# UniAdapter.net
KiCad netlist of a schematic drawn in EAGLE
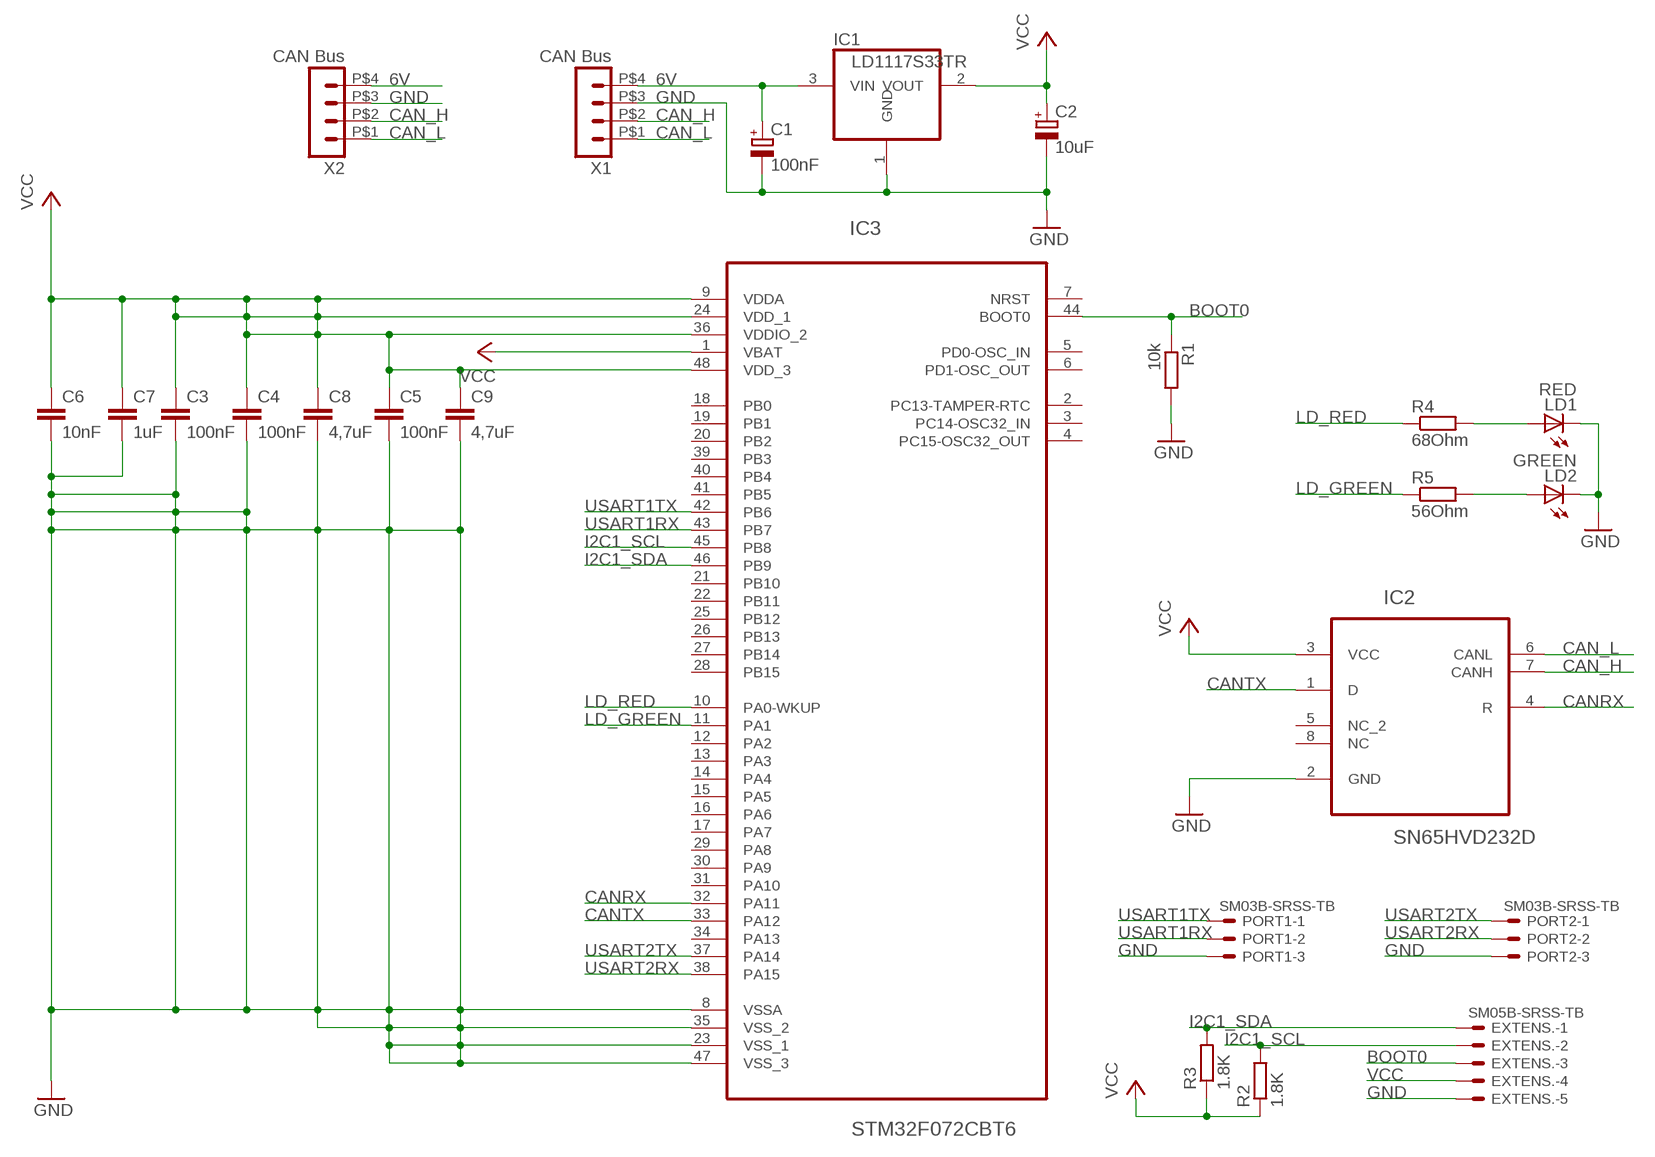
[diagram p0: schematic, sheet 1]

(export (version "E")
  (design (tool "Eeschema 10.0.6"))
  (components
    (comp (ref "C1")
      (value "100nF")
      (footprint "eagle-import:CT3216")
      (libsource (lib "eagle-import") (part "CPOL-EUCT3216"))
    )
    (comp (ref "C2")
      (value "10uF")
      (footprint "eagle-import:CT3216")
      (libsource (lib "eagle-import") (part "CPOL-EUCT3216"))
    )
    (comp (ref "C3")
      (value "100nF")
      (footprint "eagle-import:C0603")
      (libsource (lib "eagle-import") (part "C-EUC0603"))
    )
    (comp (ref "C4")
      (value "100nF")
      (footprint "eagle-import:C0603")
      (libsource (lib "eagle-import") (part "C-EUC0603"))
    )
    (comp (ref "C5")
      (value "100nF")
      (footprint "eagle-import:C0603")
      (libsource (lib "eagle-import") (part "C-EUC0603"))
    )
    (comp (ref "C6")
      (value "10nF")
      (footprint "eagle-import:C0603")
      (libsource (lib "eagle-import") (part "C-EUC0603"))
    )
    (comp (ref "C7")
      (value "1uF")
      (footprint "eagle-import:C0603")
      (libsource (lib "eagle-import") (part "C-EUC0603"))
    )
    (comp (ref "C8")
      (value "4,7uF")
      (footprint "eagle-import:C0603")
      (libsource (lib "eagle-import") (part "C-EUC0603"))
    )
    (comp (ref "C9")
      (value "4,7uF")
      (footprint "eagle-import:C0603")
      (libsource (lib "eagle-import") (part "C-EUC0603"))
    )
    (comp (ref "EXTENS.")
      (value "SM05B-SRSS-TB")
      (footprint "eagle-import:SM05B-SRSS-TB")
      (libsource (lib "eagle-import") (part "?M05B-SRSS-TBS"))
    )
    (comp (ref "IC1")
      (value "LD1117S33TR")
      (footprint "eagle-import:SOT223")
      (fields (field (name "MF") "STMICROELECTRONICS") (field (name "MPN") "REG1117"))
      (libsource (lib "eagle-import") (part "LD1117S33TR"))
    )
    (comp (ref "IC2")
      (value "SN65HVD232D")
      (footprint "eagle-import:SOIC127P600X175-8N")
      (libsource (lib "eagle-import") (part "SN65HVD232D"))
    )
    (comp (ref "IC3")
      (value "STM32F072CBT6")
      (footprint "eagle-import:LQFP48")
      (libsource (lib "eagle-import") (part "STM32F072CBT6"))
    )
    (comp (ref "LD1")
      (value "RED")
      (footprint "eagle-import:CHIPLED_0603")
      (libsource (lib "eagle-import") (part "LEDCHIPLED_0603"))
    )
    (comp (ref "LD2")
      (value "GREEN")
      (footprint "eagle-import:CHIPLED_0603")
      (libsource (lib "eagle-import") (part "LEDCHIPLED_0603"))
    )
    (comp (ref "PORT1")
      (value "SM03B-SRSS-TB")
      (footprint "eagle-import:SM03B-SRSS-TB")
      (libsource (lib "eagle-import") (part "?M03B-SRSS-TBS"))
    )
    (comp (ref "PORT2")
      (value "SM03B-SRSS-TB")
      (footprint "eagle-import:SM03B-SRSS-TB")
      (libsource (lib "eagle-import") (part "?M03B-SRSS-TBS"))
    )
    (comp (ref "R1")
      (value "10k")
      (footprint "eagle-import:R0603")
      (libsource (lib "eagle-import") (part "R-EU_R0603"))
    )
    (comp (ref "R2")
      (value "1.8K")
      (footprint "eagle-import:R0603")
      (libsource (lib "eagle-import") (part "R-EU_R0603"))
    )
    (comp (ref "R3")
      (value "1.8K")
      (footprint "eagle-import:R0603")
      (libsource (lib "eagle-import") (part "R-EU_R0603"))
    )
    (comp (ref "R4")
      (value "68Ohm")
      (footprint "eagle-import:R0603")
      (libsource (lib "eagle-import") (part "R-EU_R0603"))
    )
    (comp (ref "R5")
      (value "56Ohm")
      (footprint "eagle-import:R0603")
      (libsource (lib "eagle-import") (part "R-EU_R0603"))
    )
    (comp (ref "X1")
      (value "CAN Bus")
      (footprint "eagle-import:43650-0412")
      (libsource (lib "eagle-import") (part "HEADER_POS4_?43650-0412"))
    )
    (comp (ref "X2")
      (value "CAN Bus")
      (footprint "eagle-import:43650-0412")
      (libsource (lib "eagle-import") (part "HEADER_POS4_?43650-0412"))
    )
  )
  (nets
    (net (code "1") (name "/6V") (class "Default")
      (node (ref "C1") (pin "+") (pinfunction "+_+") (pintype "passive"))
      (node (ref "IC1") (pin "3") (pinfunction "VIN_3") (pintype "input"))
      (node (ref "X1") (pin "P$4") (pinfunction "4_P$4") (pintype "passive"))
      (node (ref "X2") (pin "P$4") (pinfunction "4_P$4") (pintype "passive"))
    )
    (net (code "2") (name "/BOOT0") (class "Default")
      (node (ref "EXTENS.") (pin "3") (pinfunction "S_3") (pintype "passive"))
      (node (ref "IC3") (pin "44") (pinfunction "BOOT0_44") (pintype "bidirectional"))
      (node (ref "R1") (pin "1") (pinfunction "1_1") (pintype "passive"))
    )
    (net (code "3") (name "/CANRX") (class "Default")
      (node (ref "IC2") (pin "4") (pinfunction "R_4") (pintype "output"))
      (node (ref "IC3") (pin "32") (pinfunction "PA11_32") (pintype "power_in"))
    )
    (net (code "4") (name "/CANTX") (class "Default")
      (node (ref "IC2") (pin "1") (pinfunction "D_1") (pintype "input"))
      (node (ref "IC3") (pin "33") (pinfunction "PA12_33") (pintype "bidirectional"))
    )
    (net (code "5") (name "/CAN_H") (class "Default")
      (node (ref "IC2") (pin "7") (pinfunction "CANH_7") (pintype "output"))
      (node (ref "X1") (pin "P$2") (pinfunction "2_P$2") (pintype "passive"))
      (node (ref "X2") (pin "P$2") (pinfunction "2_P$2") (pintype "passive"))
    )
    (net (code "6") (name "/CAN_L") (class "Default")
      (node (ref "IC2") (pin "6") (pinfunction "CANL_6") (pintype "output"))
      (node (ref "X1") (pin "P$1") (pinfunction "1_P$1") (pintype "passive"))
      (node (ref "X2") (pin "P$1") (pinfunction "1_P$1") (pintype "passive"))
    )
    (net (code "7") (name "/I2C1_SCL") (class "Default")
      (node (ref "EXTENS.") (pin "2") (pinfunction "S_2") (pintype "passive"))
      (node (ref "IC3") (pin "45") (pinfunction "PB8_45") (pintype "bidirectional"))
      (node (ref "R2") (pin "2") (pinfunction "2_2") (pintype "passive"))
    )
    (net (code "8") (name "/I2C1_SDA") (class "Default")
      (node (ref "EXTENS.") (pin "1") (pinfunction "S_1") (pintype "passive"))
      (node (ref "IC3") (pin "46") (pinfunction "PB9_46") (pintype "bidirectional"))
      (node (ref "R3") (pin "2") (pinfunction "2_2") (pintype "passive"))
    )
    (net (code "9") (name "/LD_GREEN") (class "Default")
      (node (ref "IC3") (pin "11") (pinfunction "PA1_11") (pintype "bidirectional"))
      (node (ref "R5") (pin "1") (pinfunction "1_1") (pintype "passive"))
    )
    (net (code "10") (name "/LD_RED") (class "Default")
      (node (ref "IC3") (pin "10") (pinfunction "PA0-WKUP_10") (pintype "bidirectional"))
      (node (ref "R4") (pin "1") (pinfunction "1_1") (pintype "passive"))
    )
    (net (code "11") (name "/USART1RX") (class "Default")
      (node (ref "IC3") (pin "43") (pinfunction "PB7_43") (pintype "bidirectional"))
      (node (ref "PORT1") (pin "2") (pinfunction "S_2") (pintype "passive"))
    )
    (net (code "12") (name "/USART1TX") (class "Default")
      (node (ref "IC3") (pin "42") (pinfunction "PB6_42") (pintype "bidirectional"))
      (node (ref "PORT1") (pin "1") (pinfunction "S_1") (pintype "passive"))
    )
    (net (code "13") (name "/USART2RX") (class "Default")
      (node (ref "IC3") (pin "38") (pinfunction "PA15_38") (pintype "bidirectional"))
      (node (ref "PORT2") (pin "2") (pinfunction "S_2") (pintype "passive"))
    )
    (net (code "14") (name "/USART2TX") (class "Default")
      (node (ref "IC3") (pin "37") (pinfunction "PA14_37") (pintype "bidirectional"))
      (node (ref "PORT2") (pin "1") (pinfunction "S_1") (pintype "passive"))
    )
    (net (code "15") (name "GND") (class "Default")
      (node (ref "C1") (pin "-") (pinfunction "-_-") (pintype "passive"))
      (node (ref "C2") (pin "-") (pinfunction "-_-") (pintype "passive"))
      (node (ref "C3") (pin "2") (pinfunction "2_2") (pintype "passive"))
      (node (ref "C4") (pin "2") (pinfunction "2_2") (pintype "passive"))
      (node (ref "C5") (pin "2") (pinfunction "2_2") (pintype "passive"))
      (node (ref "C6") (pin "2") (pinfunction "2_2") (pintype "passive"))
      (node (ref "C7") (pin "2") (pinfunction "2_2") (pintype "passive"))
      (node (ref "C8") (pin "2") (pinfunction "2_2") (pintype "passive"))
      (node (ref "C9") (pin "2") (pinfunction "2_2") (pintype "passive"))
      (node (ref "EXTENS.") (pin "5") (pinfunction "S_5") (pintype "passive"))
      (node (ref "IC1") (pin "1") (pinfunction "GND_1") (pintype "power_in"))
      (node (ref "IC2") (pin "2") (pinfunction "GND_2") (pintype "passive"))
      (node (ref "IC3") (pin "23") (pinfunction "VSS_1_23") (pintype "bidirectional"))
      (node (ref "IC3") (pin "35") (pinfunction "VSS_2_35") (pintype "passive"))
      (node (ref "IC3") (pin "47") (pinfunction "VSS_3_47") (pintype "passive"))
      (node (ref "IC3") (pin "8") (pinfunction "VSSA_8") (pintype "passive"))
      (node (ref "LD1") (pin "C") (pinfunction "C_C") (pintype "passive"))
      (node (ref "LD2") (pin "C") (pinfunction "C_C") (pintype "passive"))
      (node (ref "PORT1") (pin "3") (pinfunction "S_3") (pintype "passive"))
      (node (ref "PORT2") (pin "3") (pinfunction "S_3") (pintype "passive"))
      (node (ref "R1") (pin "2") (pinfunction "2_2") (pintype "passive"))
      (node (ref "X1") (pin "P$3") (pinfunction "3_P$3") (pintype "passive"))
      (node (ref "X2") (pin "P$3") (pinfunction "3_P$3") (pintype "passive"))
    )
    (net (code "16") (name "Net-(LD1-PadA)") (class "Default")
      (node (ref "LD1") (pin "A") (pinfunction "A_A") (pintype "passive"))
      (node (ref "R4") (pin "2") (pinfunction "2_2") (pintype "passive"))
    )
    (net (code "17") (name "Net-(LD2-PadA)") (class "Default")
      (node (ref "LD2") (pin "A") (pinfunction "A_A") (pintype "passive"))
      (node (ref "R5") (pin "2") (pinfunction "2_2") (pintype "passive"))
    )
    (net (code "18") (name "VCC") (class "Default")
      (node (ref "C2") (pin "+") (pinfunction "+_+") (pintype "passive"))
      (node (ref "C3") (pin "1") (pinfunction "1_1") (pintype "passive"))
      (node (ref "C4") (pin "1") (pinfunction "1_1") (pintype "passive"))
      (node (ref "C5") (pin "1") (pinfunction "1_1") (pintype "passive"))
      (node (ref "C6") (pin "1") (pinfunction "1_1") (pintype "passive"))
      (node (ref "C7") (pin "1") (pinfunction "1_1") (pintype "passive"))
      (node (ref "C8") (pin "1") (pinfunction "1_1") (pintype "passive"))
      (node (ref "C9") (pin "1") (pinfunction "1_1") (pintype "passive"))
      (node (ref "EXTENS.") (pin "4") (pinfunction "S_4") (pintype "passive"))
      (node (ref "IC1") (pin "2") (pinfunction "VOUT_2") (pintype "output"))
      (node (ref "IC2") (pin "3") (pinfunction "VCC_3") (pintype "power_in"))
      (node (ref "IC3") (pin "1") (pinfunction "VBAT_1") (pintype "input"))
      (node (ref "IC3") (pin "24") (pinfunction "VDD_1_24") (pintype "bidirectional"))
      (node (ref "IC3") (pin "36") (pinfunction "VDDIO_2_36") (pintype "power_in"))
      (node (ref "IC3") (pin "48") (pinfunction "VDD_3_48") (pintype "power_in"))
      (node (ref "IC3") (pin "9") (pinfunction "VDDA_9") (pintype "power_in"))
      (node (ref "R2") (pin "1") (pinfunction "1_1") (pintype "passive"))
      (node (ref "R3") (pin "1") (pinfunction "1_1") (pintype "passive"))
    )
    (net (code "19") (name "unconnected-(IC2-NC-Pad8)") (class "Default")
      (node (ref "IC2") (pin "8") (pinfunction "NC_8") (pintype "no_connect"))
    )
    (net (code "20") (name "unconnected-(IC2-NC_2-Pad5)") (class "Default")
      (node (ref "IC2") (pin "5") (pinfunction "NC_2_5") (pintype "no_connect"))
    )
    (net (code "21") (name "unconnected-(IC3-NRST-Pad7)") (class "Default")
      (node (ref "IC3") (pin "7") (pinfunction "NRST_7") (pintype "bidirectional"))
    )
    (net (code "22") (name "unconnected-(IC3-PA2-Pad12)") (class "Default")
      (node (ref "IC3") (pin "12") (pinfunction "PA2_12") (pintype "bidirectional"))
    )
    (net (code "23") (name "unconnected-(IC3-PA3-Pad13)") (class "Default")
      (node (ref "IC3") (pin "13") (pinfunction "PA3_13") (pintype "bidirectional"))
    )
    (net (code "24") (name "unconnected-(IC3-PA4-Pad14)") (class "Default")
      (node (ref "IC3") (pin "14") (pinfunction "PA4_14") (pintype "bidirectional"))
    )
    (net (code "25") (name "unconnected-(IC3-PA5-Pad15)") (class "Default")
      (node (ref "IC3") (pin "15") (pinfunction "PA5_15") (pintype "bidirectional"))
    )
    (net (code "26") (name "unconnected-(IC3-PA6-Pad16)") (class "Default")
      (node (ref "IC3") (pin "16") (pinfunction "PA6_16") (pintype "bidirectional"))
    )
    (net (code "27") (name "unconnected-(IC3-PA7-Pad17)") (class "Default")
      (node (ref "IC3") (pin "17") (pinfunction "PA7_17") (pintype "bidirectional"))
    )
    (net (code "28") (name "unconnected-(IC3-PA8-Pad29)") (class "Default")
      (node (ref "IC3") (pin "29") (pinfunction "PA8_29") (pintype "bidirectional"))
    )
    (net (code "29") (name "unconnected-(IC3-PA9-Pad30)") (class "Default")
      (node (ref "IC3") (pin "30") (pinfunction "PA9_30") (pintype "bidirectional"))
    )
    (net (code "30") (name "unconnected-(IC3-PA10-Pad31)") (class "Default")
      (node (ref "IC3") (pin "31") (pinfunction "PA10_31") (pintype "bidirectional"))
    )
    (net (code "31") (name "unconnected-(IC3-PA13-Pad34)") (class "Default")
      (node (ref "IC3") (pin "34") (pinfunction "PA13_34") (pintype "bidirectional"))
    )
    (net (code "32") (name "unconnected-(IC3-PB0-Pad18)") (class "Default")
      (node (ref "IC3") (pin "18") (pinfunction "PB0_18") (pintype "bidirectional"))
    )
    (net (code "33") (name "unconnected-(IC3-PB1-Pad19)") (class "Default")
      (node (ref "IC3") (pin "19") (pinfunction "PB1_19") (pintype "bidirectional"))
    )
    (net (code "34") (name "unconnected-(IC3-PB2-Pad20)") (class "Default")
      (node (ref "IC3") (pin "20") (pinfunction "PB2_20") (pintype "bidirectional"))
    )
    (net (code "35") (name "unconnected-(IC3-PB3-Pad39)") (class "Default")
      (node (ref "IC3") (pin "39") (pinfunction "PB3_39") (pintype "bidirectional"))
    )
    (net (code "36") (name "unconnected-(IC3-PB4-Pad40)") (class "Default")
      (node (ref "IC3") (pin "40") (pinfunction "PB4_40") (pintype "bidirectional"))
    )
    (net (code "37") (name "unconnected-(IC3-PB5-Pad41)") (class "Default")
      (node (ref "IC3") (pin "41") (pinfunction "PB5_41") (pintype "bidirectional"))
    )
    (net (code "38") (name "unconnected-(IC3-PB10-Pad21)") (class "Default")
      (node (ref "IC3") (pin "21") (pinfunction "PB10_21") (pintype "bidirectional"))
    )
    (net (code "39") (name "unconnected-(IC3-PB11-Pad22)") (class "Default")
      (node (ref "IC3") (pin "22") (pinfunction "PB11_22") (pintype "bidirectional"))
    )
    (net (code "40") (name "unconnected-(IC3-PB12-Pad25)") (class "Default")
      (node (ref "IC3") (pin "25") (pinfunction "PB12_25") (pintype "bidirectional"))
    )
    (net (code "41") (name "unconnected-(IC3-PB13-Pad26)") (class "Default")
      (node (ref "IC3") (pin "26") (pinfunction "PB13_26") (pintype "bidirectional"))
    )
    (net (code "42") (name "unconnected-(IC3-PB14-Pad27)") (class "Default")
      (node (ref "IC3") (pin "27") (pinfunction "PB14_27") (pintype "bidirectional"))
    )
    (net (code "43") (name "unconnected-(IC3-PB15-Pad28)") (class "Default")
      (node (ref "IC3") (pin "28") (pinfunction "PB15_28") (pintype "bidirectional"))
    )
    (net (code "44") (name "unconnected-(IC3-PC13-TAMPER-RTC-Pad2)") (class "Default")
      (node (ref "IC3") (pin "2") (pinfunction "PC13-TAMPER-RTC_2") (pintype "bidirectional"))
    )
    (net (code "45") (name "unconnected-(IC3-PC14-OSC32_IN-Pad3)") (class "Default")
      (node (ref "IC3") (pin "3") (pinfunction "PC14-OSC32_IN_3") (pintype "bidirectional"))
    )
    (net (code "46") (name "unconnected-(IC3-PC15-OSC32_OUT-Pad4)") (class "Default")
      (node (ref "IC3") (pin "4") (pinfunction "PC15-OSC32_OUT_4") (pintype "bidirectional"))
    )
    (net (code "47") (name "unconnected-(IC3-PD0-OSC_IN-Pad5)") (class "Default")
      (node (ref "IC3") (pin "5") (pinfunction "PD0-OSC_IN_5") (pintype "bidirectional"))
    )
    (net (code "48") (name "unconnected-(IC3-PD1-OSC_OUT-Pad6)") (class "Default")
      (node (ref "IC3") (pin "6") (pinfunction "PD1-OSC_OUT_6") (pintype "bidirectional"))
    )
  )
)
